# 3.net
KiCad netlist of a schematic drawn in Altium Designer
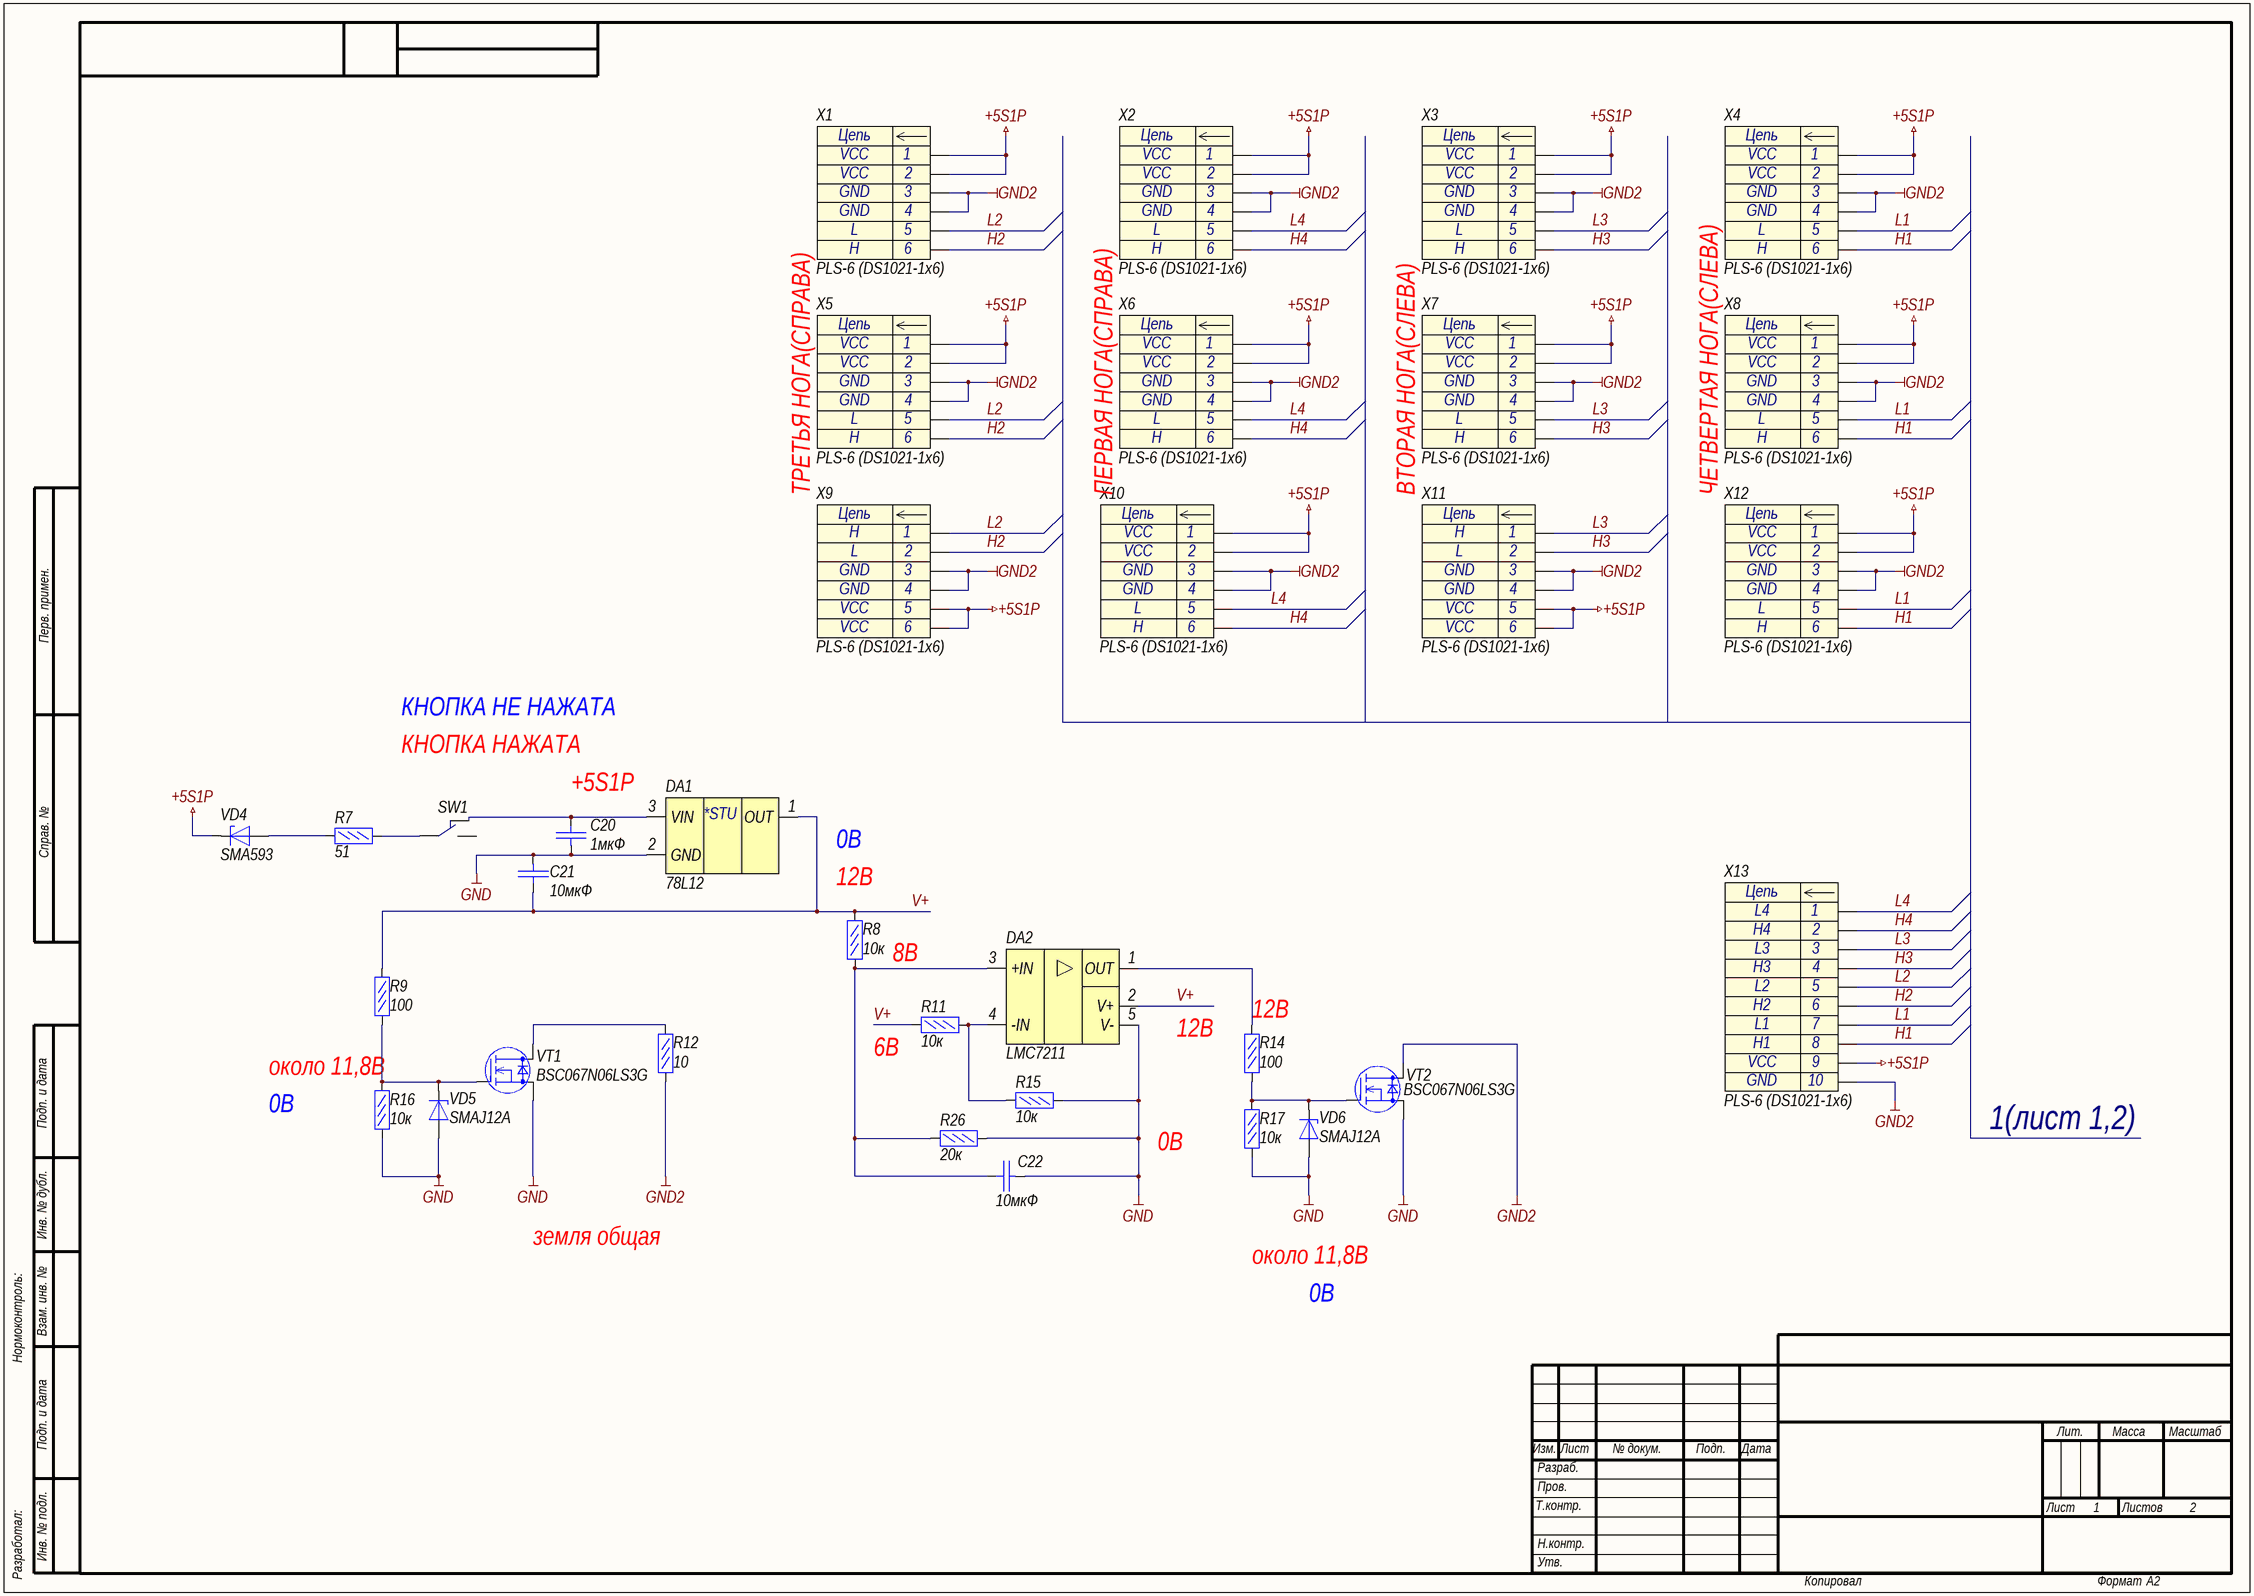
[diagram p0: Э3.SchDoc]

(export (version "E")
  (design (tool "Eeschema 10.0.6"))
  (components
    (comp (ref "C20")
      (value "1мкФ")
      (footprint "C0603")
      (description "Конденсатор керамический 0603")
      (libsource (lib "capacitors") (part "C0603"))
    )
    (comp (ref "C21")
      (value "10мкФ")
      (footprint "C0603")
      (description "Конденсатор керамический 0603")
      (libsource (lib "capacitors") (part "C0603"))
    )
    (comp (ref "C22")
      (value "10мкФ")
      (footprint "C0603")
      (description "Конденсатор керамический 0603")
      (libsource (lib "capacitors") (part "C0603"))
    )
    (comp (ref "DA1")
      (value "78L12")
      (footprint "D-PAK")
      (description "Линейный стабилизатор напряжения 3,3В")
      (fields (field (name "MANUFACTURER") "Texas Instruments"))
      (libsource (lib "ics") (part "78L12"))
    )
    (comp (ref "DA2")
      (value "LMC7211")
      (footprint "SOT23-5")
      (description "Компаратор")
      (fields (field (name "MANUFACTURER") "Analog Devices"))
      (libsource (lib "ics") (part "LMC7211"))
    )
    (comp (ref "R7")
      (value "51")
      (footprint "R0603")
      (description "Резистор 47кОм 0,063Вт 1%")
      (fields (field (name "MANUFACTURER") "YAGEO") (field (name "TOLERANCE") "1%"))
      (libsource (lib "resistors") (part "RC0603FR-0715KL_1"))
    )
    (comp (ref "R8")
      (value "10к")
      (footprint "R0603")
      (description "Резистор 47кОм 0,063Вт 1%")
      (fields (field (name "MANUFACTURER") "YAGEO") (field (name "TOLERANCE") "1%"))
      (libsource (lib "") (part "RC0603FR-0715KL_1_1"))
    )
    (comp (ref "R9")
      (value "100")
      (footprint "R0603")
      (description "Резистор 47кОм 0,063Вт 1%")
      (fields (field (name "MANUFACTURER") "YAGEO") (field (name "TOLERANCE") "1%"))
      (libsource (lib "") (part "RC0603FR-0715KL_1_2"))
    )
    (comp (ref "R11")
      (value "10к")
      (footprint "R0603")
      (description "Резистор 47кОм 0,063Вт 1%")
      (fields (field (name "MANUFACTURER") "YAGEO") (field (name "TOLERANCE") "1%"))
      (libsource (lib "resistors") (part "RC0603FR-0715KL_1"))
    )
    (comp (ref "R12")
      (value "10")
      (footprint "R0603")
      (description "Резистор 47кОм 0,063Вт 1%")
      (fields (field (name "MANUFACTURER") "YAGEO") (field (name "TOLERANCE") "1%"))
      (libsource (lib "") (part "RC0603FR-0715KL_1_1"))
    )
    (comp (ref "R14")
      (value "100")
      (footprint "R0603")
      (description "Резистор 100 Ом 0,1Вт 1%")
      (fields (field (name "MANUFACTURER") "YAGEO") (field (name "TOLERANCE") "1%"))
      (libsource (lib "resistors") (part "RC0603FR-07100RL"))
    )
    (comp (ref "R15")
      (value "10к")
      (footprint "R0603")
      (description "Резистор 47кОм 0,063Вт 1%")
      (fields (field (name "MANUFACTURER") "YAGEO") (field (name "TOLERANCE") "1%"))
      (libsource (lib "") (part "RC0603FR-0715KL_1_3"))
    )
    (comp (ref "R16")
      (value "10к")
      (footprint "R0603")
      (description "Резистор 47кОм 0,063Вт 1%")
      (fields (field (name "MANUFACTURER") "YAGEO") (field (name "TOLERANCE") "1%"))
      (libsource (lib "") (part "RC0603FR-0715KL_1_1"))
    )
    (comp (ref "R17")
      (value "10к")
      (footprint "R0603")
      (description "Резистор 47кОм 0,063Вт 1%")
      (fields (field (name "MANUFACTURER") "YAGEO") (field (name "TOLERANCE") "1%"))
      (libsource (lib "") (part "RC0603FR-0715KL_1_2"))
    )
    (comp (ref "R26")
      (value "20к")
      (footprint "R0603")
      (description "Резистор 47кОм 0,063Вт 1%")
      (fields (field (name "MANUFACTURER") "YAGEO") (field (name "TOLERANCE") "1%"))
      (libsource (lib "resistors") (part "RC0603FR-0715KL_1"))
    )
    (comp (ref "SW1")
      (value "кнопка_S")
      (footprint "SWITCH")
      (description "крутые переключатели с бимов")
      (libsource (lib "LibraryPloshchadnaia") (part "BT992895"))
    )
    (comp (ref "VD4")
      (value "SMA593")
      (description "Диод защитный 12В")
      (libsource (lib "diodes") (part "SMAJ12A"))
    )
    (comp (ref "VD5")
      (value "SMAJ12A")
      (description "Диод защитный 12В")
      (libsource (lib "diodes") (part "SMAJ12A"))
    )
    (comp (ref "VD6")
      (value "SMAJ12A")
      (description "Диод защитный 12В")
      (libsource (lib "diodes") (part "SMAJ12A"))
    )
    (comp (ref "VT1")
      (value "BSC067N06LS3G")
      (description "N-MOSFET")
      (libsource (lib "transistors") (part "N-MOSFET"))
    )
    (comp (ref "VT2")
      (value "BSC067N06LS3G")
      (description "N-MOSFET")
      (libsource (lib "transistors") (part "N-MOSFET"))
    )
    (comp (ref "X1")
      (value "PLS-6 (DS1021-1x6)")
      (footprint "PLS-6")
      (description "Разъем - 6 конт. прямая вилка на плату, шаг 2,54 мм")
      (libsource (lib "headers") (part "PLS-6"))
    )
    (comp (ref "X2")
      (value "PLS-6 (DS1021-1x6)")
      (footprint "PLS-6")
      (description "Разъем - 6 конт. прямая вилка на плату, шаг 2,54 мм")
      (libsource (lib "headers") (part "PLS-6"))
    )
    (comp (ref "X3")
      (value "PLS-6 (DS1021-1x6)")
      (footprint "PLS-6")
      (description "Разъем - 6 конт. прямая вилка на плату, шаг 2,54 мм")
      (libsource (lib "headers") (part "PLS-6"))
    )
    (comp (ref "X4")
      (value "PLS-6 (DS1021-1x6)")
      (footprint "PLS-6")
      (description "Разъем - 6 конт. прямая вилка на плату, шаг 2,54 мм")
      (libsource (lib "headers") (part "PLS-6"))
    )
    (comp (ref "X5")
      (value "PLS-6 (DS1021-1x6)")
      (footprint "PLS-6")
      (description "Разъем - 6 конт. прямая вилка на плату, шаг 2,54 мм")
      (libsource (lib "headers") (part "PLS-6"))
    )
    (comp (ref "X6")
      (value "PLS-6 (DS1021-1x6)")
      (footprint "PLS-6")
      (description "Разъем - 6 конт. прямая вилка на плату, шаг 2,54 мм")
      (libsource (lib "headers") (part "PLS-6"))
    )
    (comp (ref "X7")
      (value "PLS-6 (DS1021-1x6)")
      (footprint "PLS-6")
      (description "Разъем - 6 конт. прямая вилка на плату, шаг 2,54 мм")
      (libsource (lib "headers") (part "PLS-6"))
    )
    (comp (ref "X8")
      (value "PLS-6 (DS1021-1x6)")
      (footprint "PLS-6")
      (description "Разъем - 6 конт. прямая вилка на плату, шаг 2,54 мм")
      (libsource (lib "headers") (part "PLS-6"))
    )
    (comp (ref "X9")
      (value "PLS-6 (DS1021-1x6)")
      (footprint "PLS-6")
      (description "Разъем - 6 конт. прямая вилка на плату, шаг 2,54 мм")
      (libsource (lib "headers") (part "PLS-6"))
    )
    (comp (ref "X10")
      (value "PLS-6 (DS1021-1x6)")
      (footprint "PLS-6")
      (description "Разъем - 6 конт. прямая вилка на плату, шаг 2,54 мм")
      (libsource (lib "headers") (part "PLS-6"))
    )
    (comp (ref "X11")
      (value "PLS-6 (DS1021-1x6)")
      (footprint "PLS-6")
      (description "Разъем - 6 конт. прямая вилка на плату, шаг 2,54 мм")
      (libsource (lib "headers") (part "PLS-6"))
    )
    (comp (ref "X12")
      (value "PLS-6 (DS1021-1x6)")
      (footprint "PLS-6")
      (description "Разъем - 6 конт. прямая вилка на плату, шаг 2,54 мм")
      (libsource (lib "headers") (part "PLS-6"))
    )
    (comp (ref "X13")
      (value "PLS-6 (DS1021-1x6)")
      (footprint "PLS-6")
      (description "Разъем - 10 конт. прямая вилка на плату, шаг 2,54 мм")
      (libsource (lib "headers") (part "PLS-10"))
    )
  )
  (nets
    (net (code "1") (name "+5S1P") (class "Default")
      (node (ref "VD4") (pin "1") (pinfunction "K_1") (pintype "passive"))
      (node (ref "X1") (pin "1") (pinfunction "1_1") (pintype "passive"))
      (node (ref "X1") (pin "2") (pinfunction "2_2") (pintype "passive"))
      (node (ref "X10") (pin "1") (pinfunction "1_1") (pintype "passive"))
      (node (ref "X10") (pin "2") (pinfunction "2_2") (pintype "passive"))
      (node (ref "X11") (pin "5") (pinfunction "5_5") (pintype "passive"))
      (node (ref "X11") (pin "6") (pinfunction "6_6") (pintype "passive"))
      (node (ref "X12") (pin "1") (pinfunction "1_1") (pintype "passive"))
      (node (ref "X12") (pin "2") (pinfunction "2_2") (pintype "passive"))
      (node (ref "X13") (pin "9") (pinfunction "9_9") (pintype "passive"))
      (node (ref "X2") (pin "1") (pinfunction "1_1") (pintype "passive"))
      (node (ref "X2") (pin "2") (pinfunction "2_2") (pintype "passive"))
      (node (ref "X3") (pin "1") (pinfunction "1_1") (pintype "passive"))
      (node (ref "X3") (pin "2") (pinfunction "2_2") (pintype "passive"))
      (node (ref "X4") (pin "1") (pinfunction "1_1") (pintype "passive"))
      (node (ref "X4") (pin "2") (pinfunction "2_2") (pintype "passive"))
      (node (ref "X5") (pin "1") (pinfunction "1_1") (pintype "passive"))
      (node (ref "X5") (pin "2") (pinfunction "2_2") (pintype "passive"))
      (node (ref "X6") (pin "1") (pinfunction "1_1") (pintype "passive"))
      (node (ref "X6") (pin "2") (pinfunction "2_2") (pintype "passive"))
      (node (ref "X7") (pin "1") (pinfunction "1_1") (pintype "passive"))
      (node (ref "X7") (pin "2") (pinfunction "2_2") (pintype "passive"))
      (node (ref "X8") (pin "1") (pinfunction "1_1") (pintype "passive"))
      (node (ref "X8") (pin "2") (pinfunction "2_2") (pintype "passive"))
      (node (ref "X9") (pin "5") (pinfunction "5_5") (pintype "passive"))
      (node (ref "X9") (pin "6") (pinfunction "6_6") (pintype "passive"))
    )
    (net (code "2") (name "/H1") (class "Default")
      (node (ref "X12") (pin "6") (pinfunction "6_6") (pintype "passive"))
      (node (ref "X13") (pin "8") (pinfunction "8_8") (pintype "passive"))
      (node (ref "X4") (pin "6") (pinfunction "6_6") (pintype "passive"))
      (node (ref "X8") (pin "6") (pinfunction "6_6") (pintype "passive"))
    )
    (net (code "3") (name "/H2") (class "Default")
      (node (ref "X1") (pin "6") (pinfunction "6_6") (pintype "passive"))
      (node (ref "X13") (pin "6") (pinfunction "6_6") (pintype "passive"))
      (node (ref "X5") (pin "6") (pinfunction "6_6") (pintype "passive"))
      (node (ref "X9") (pin "2") (pinfunction "2_2") (pintype "passive"))
    )
    (net (code "4") (name "/H3") (class "Default")
      (node (ref "X11") (pin "2") (pinfunction "2_2") (pintype "passive"))
      (node (ref "X13") (pin "4") (pinfunction "4_4") (pintype "passive"))
      (node (ref "X3") (pin "6") (pinfunction "6_6") (pintype "passive"))
      (node (ref "X7") (pin "6") (pinfunction "6_6") (pintype "passive"))
    )
    (net (code "5") (name "/H4") (class "Default")
      (node (ref "X10") (pin "6") (pinfunction "6_6") (pintype "passive"))
      (node (ref "X13") (pin "2") (pinfunction "2_2") (pintype "passive"))
      (node (ref "X2") (pin "6") (pinfunction "6_6") (pintype "passive"))
      (node (ref "X6") (pin "6") (pinfunction "6_6") (pintype "passive"))
    )
    (net (code "6") (name "/L1") (class "Default")
      (node (ref "X12") (pin "5") (pinfunction "5_5") (pintype "passive"))
      (node (ref "X13") (pin "7") (pinfunction "7_7") (pintype "passive"))
      (node (ref "X4") (pin "5") (pinfunction "5_5") (pintype "passive"))
      (node (ref "X8") (pin "5") (pinfunction "5_5") (pintype "passive"))
    )
    (net (code "7") (name "/L2") (class "Default")
      (node (ref "X1") (pin "5") (pinfunction "5_5") (pintype "passive"))
      (node (ref "X13") (pin "5") (pinfunction "5_5") (pintype "passive"))
      (node (ref "X5") (pin "5") (pinfunction "5_5") (pintype "passive"))
      (node (ref "X9") (pin "1") (pinfunction "1_1") (pintype "passive"))
    )
    (net (code "8") (name "/L3") (class "Default")
      (node (ref "X11") (pin "1") (pinfunction "1_1") (pintype "passive"))
      (node (ref "X13") (pin "3") (pinfunction "3_3") (pintype "passive"))
      (node (ref "X3") (pin "5") (pinfunction "5_5") (pintype "passive"))
      (node (ref "X7") (pin "5") (pinfunction "5_5") (pintype "passive"))
    )
    (net (code "9") (name "/L4") (class "Default")
      (node (ref "X10") (pin "5") (pinfunction "5_5") (pintype "passive"))
      (node (ref "X13") (pin "1") (pinfunction "1_1") (pintype "passive"))
      (node (ref "X2") (pin "5") (pinfunction "5_5") (pintype "passive"))
      (node (ref "X6") (pin "5") (pinfunction "5_5") (pintype "passive"))
    )
    (net (code "10") (name "/V+") (class "Default")
      (node (ref "C21") (pin "1") (pinfunction "1_1") (pintype "passive"))
      (node (ref "DA1") (pin "1") (pinfunction "OUT_1") (pintype "passive"))
      (node (ref "DA2") (pin "2") (pinfunction "V+_2") (pintype "passive"))
      (node (ref "R11") (pin "1") (pinfunction "1_1") (pintype "passive"))
      (node (ref "R8") (pin "1") (pinfunction "1_1") (pintype "passive"))
      (node (ref "R9") (pin "2") (pinfunction "2_2") (pintype "passive"))
    )
    (net (code "11") (name "GND") (class "Default")
      (node (ref "C20") (pin "2") (pinfunction "2_2") (pintype "passive"))
      (node (ref "C21") (pin "2") (pinfunction "2_2") (pintype "passive"))
      (node (ref "C22") (pin "2") (pinfunction "2_2") (pintype "passive"))
      (node (ref "DA1") (pin "2") (pinfunction "GND_2") (pintype "passive"))
      (node (ref "DA2") (pin "5") (pinfunction "V-_5") (pintype "passive"))
      (node (ref "R15") (pin "1") (pinfunction "1_1") (pintype "passive"))
      (node (ref "R16") (pin "2") (pinfunction "2_2") (pintype "passive"))
      (node (ref "R17") (pin "1") (pinfunction "1_1") (pintype "passive"))
      (node (ref "R26") (pin "2") (pinfunction "2_2") (pintype "passive"))
      (node (ref "VD5") (pin "2") (pinfunction "A_2") (pintype "passive"))
      (node (ref "VD6") (pin "2") (pinfunction "A_2") (pintype "passive"))
      (node (ref "VT1") (pin "3") (pinfunction "S_3") (pintype "passive"))
      (node (ref "VT2") (pin "3") (pinfunction "S_3") (pintype "passive"))
    )
    (net (code "12") (name "GND2") (class "Default")
      (node (ref "R12") (pin "2") (pinfunction "2_2") (pintype "passive"))
      (node (ref "VT2") (pin "2") (pinfunction "D_2") (pintype "passive"))
      (node (ref "X1") (pin "3") (pinfunction "3_3") (pintype "passive"))
      (node (ref "X1") (pin "4") (pinfunction "4_4") (pintype "passive"))
      (node (ref "X10") (pin "3") (pinfunction "3_3") (pintype "passive"))
      (node (ref "X10") (pin "4") (pinfunction "4_4") (pintype "passive"))
      (node (ref "X11") (pin "3") (pinfunction "3_3") (pintype "passive"))
      (node (ref "X11") (pin "4") (pinfunction "4_4") (pintype "passive"))
      (node (ref "X12") (pin "3") (pinfunction "3_3") (pintype "passive"))
      (node (ref "X12") (pin "4") (pinfunction "4_4") (pintype "passive"))
      (node (ref "X13") (pin "10") (pinfunction "10_10") (pintype "passive"))
      (node (ref "X2") (pin "3") (pinfunction "3_3") (pintype "passive"))
      (node (ref "X2") (pin "4") (pinfunction "4_4") (pintype "passive"))
      (node (ref "X3") (pin "3") (pinfunction "3_3") (pintype "passive"))
      (node (ref "X3") (pin "4") (pinfunction "4_4") (pintype "passive"))
      (node (ref "X4") (pin "3") (pinfunction "3_3") (pintype "passive"))
      (node (ref "X4") (pin "4") (pinfunction "4_4") (pintype "passive"))
      (node (ref "X5") (pin "3") (pinfunction "3_3") (pintype "passive"))
      (node (ref "X5") (pin "4") (pinfunction "4_4") (pintype "passive"))
      (node (ref "X6") (pin "3") (pinfunction "3_3") (pintype "passive"))
      (node (ref "X6") (pin "4") (pinfunction "4_4") (pintype "passive"))
      (node (ref "X7") (pin "3") (pinfunction "3_3") (pintype "passive"))
      (node (ref "X7") (pin "4") (pinfunction "4_4") (pintype "passive"))
      (node (ref "X8") (pin "3") (pinfunction "3_3") (pintype "passive"))
      (node (ref "X8") (pin "4") (pinfunction "4_4") (pintype "passive"))
      (node (ref "X9") (pin "3") (pinfunction "3_3") (pintype "passive"))
      (node (ref "X9") (pin "4") (pinfunction "4_4") (pintype "passive"))
    )
    (net (code "13") (name "Net-(DA1-VIN)") (class "Default")
      (node (ref "C20") (pin "1") (pinfunction "1_1") (pintype "passive"))
      (node (ref "DA1") (pin "3") (pinfunction "VIN_3") (pintype "passive"))
      (node (ref "SW1") (pin "3") (pinfunction "3_3") (pintype "passive"))
    )
    (net (code "14") (name "Net-(DA2-+IN)") (class "Default")
      (node (ref "C22") (pin "1") (pinfunction "1_1") (pintype "passive"))
      (node (ref "DA2") (pin "3") (pinfunction "+IN_3") (pintype "passive"))
      (node (ref "R26") (pin "1") (pinfunction "1_1") (pintype "passive"))
      (node (ref "R8") (pin "2") (pinfunction "2_2") (pintype "passive"))
    )
    (net (code "15") (name "Net-(DA2--IN)") (class "Default")
      (node (ref "DA2") (pin "4") (pinfunction "-IN_4") (pintype "passive"))
      (node (ref "R11") (pin "2") (pinfunction "2_2") (pintype "passive"))
      (node (ref "R15") (pin "2") (pinfunction "2_2") (pintype "passive"))
    )
    (net (code "16") (name "Net-(DA2-OUT)") (class "Default")
      (node (ref "DA2") (pin "1") (pinfunction "OUT_1") (pintype "passive"))
      (node (ref "R14") (pin "2") (pinfunction "2_2") (pintype "passive"))
    )
    (net (code "17") (name "Net-(R7-Pad2)") (class "Default")
      (node (ref "R7") (pin "2") (pinfunction "2_2") (pintype "passive"))
      (node (ref "SW1") (pin "2") (pinfunction "2_2") (pintype "passive"))
    )
    (net (code "18") (name "Net-(VD4-A)") (class "Default")
      (node (ref "R7") (pin "1") (pinfunction "1_1") (pintype "passive"))
      (node (ref "VD4") (pin "2") (pinfunction "A_2") (pintype "passive"))
    )
    (net (code "19") (name "Net-(VD5-K)") (class "Default")
      (node (ref "R16") (pin "1") (pinfunction "1_1") (pintype "passive"))
      (node (ref "R9") (pin "1") (pinfunction "1_1") (pintype "passive"))
      (node (ref "VD5") (pin "1") (pinfunction "K_1") (pintype "passive"))
      (node (ref "VT1") (pin "1") (pinfunction "G_1") (pintype "passive"))
    )
    (net (code "20") (name "Net-(VD6-K)") (class "Default")
      (node (ref "R14") (pin "1") (pinfunction "1_1") (pintype "passive"))
      (node (ref "R17") (pin "2") (pinfunction "2_2") (pintype "passive"))
      (node (ref "VD6") (pin "1") (pinfunction "K_1") (pintype "passive"))
      (node (ref "VT2") (pin "1") (pinfunction "G_1") (pintype "passive"))
    )
    (net (code "21") (name "Net-(VT1-D)") (class "Default")
      (node (ref "R12") (pin "1") (pinfunction "1_1") (pintype "passive"))
      (node (ref "VT1") (pin "2") (pinfunction "D_2") (pintype "passive"))
    )
    (net (code "22") (name "unconnected-(SW1-Pad1)") (class "Default")
      (node (ref "SW1") (pin "1") (pinfunction "1_1") (pintype "passive"))
    )
  )
)
